# Board-Front.net
KiCad netlist of a schematic drawn in EAGLE
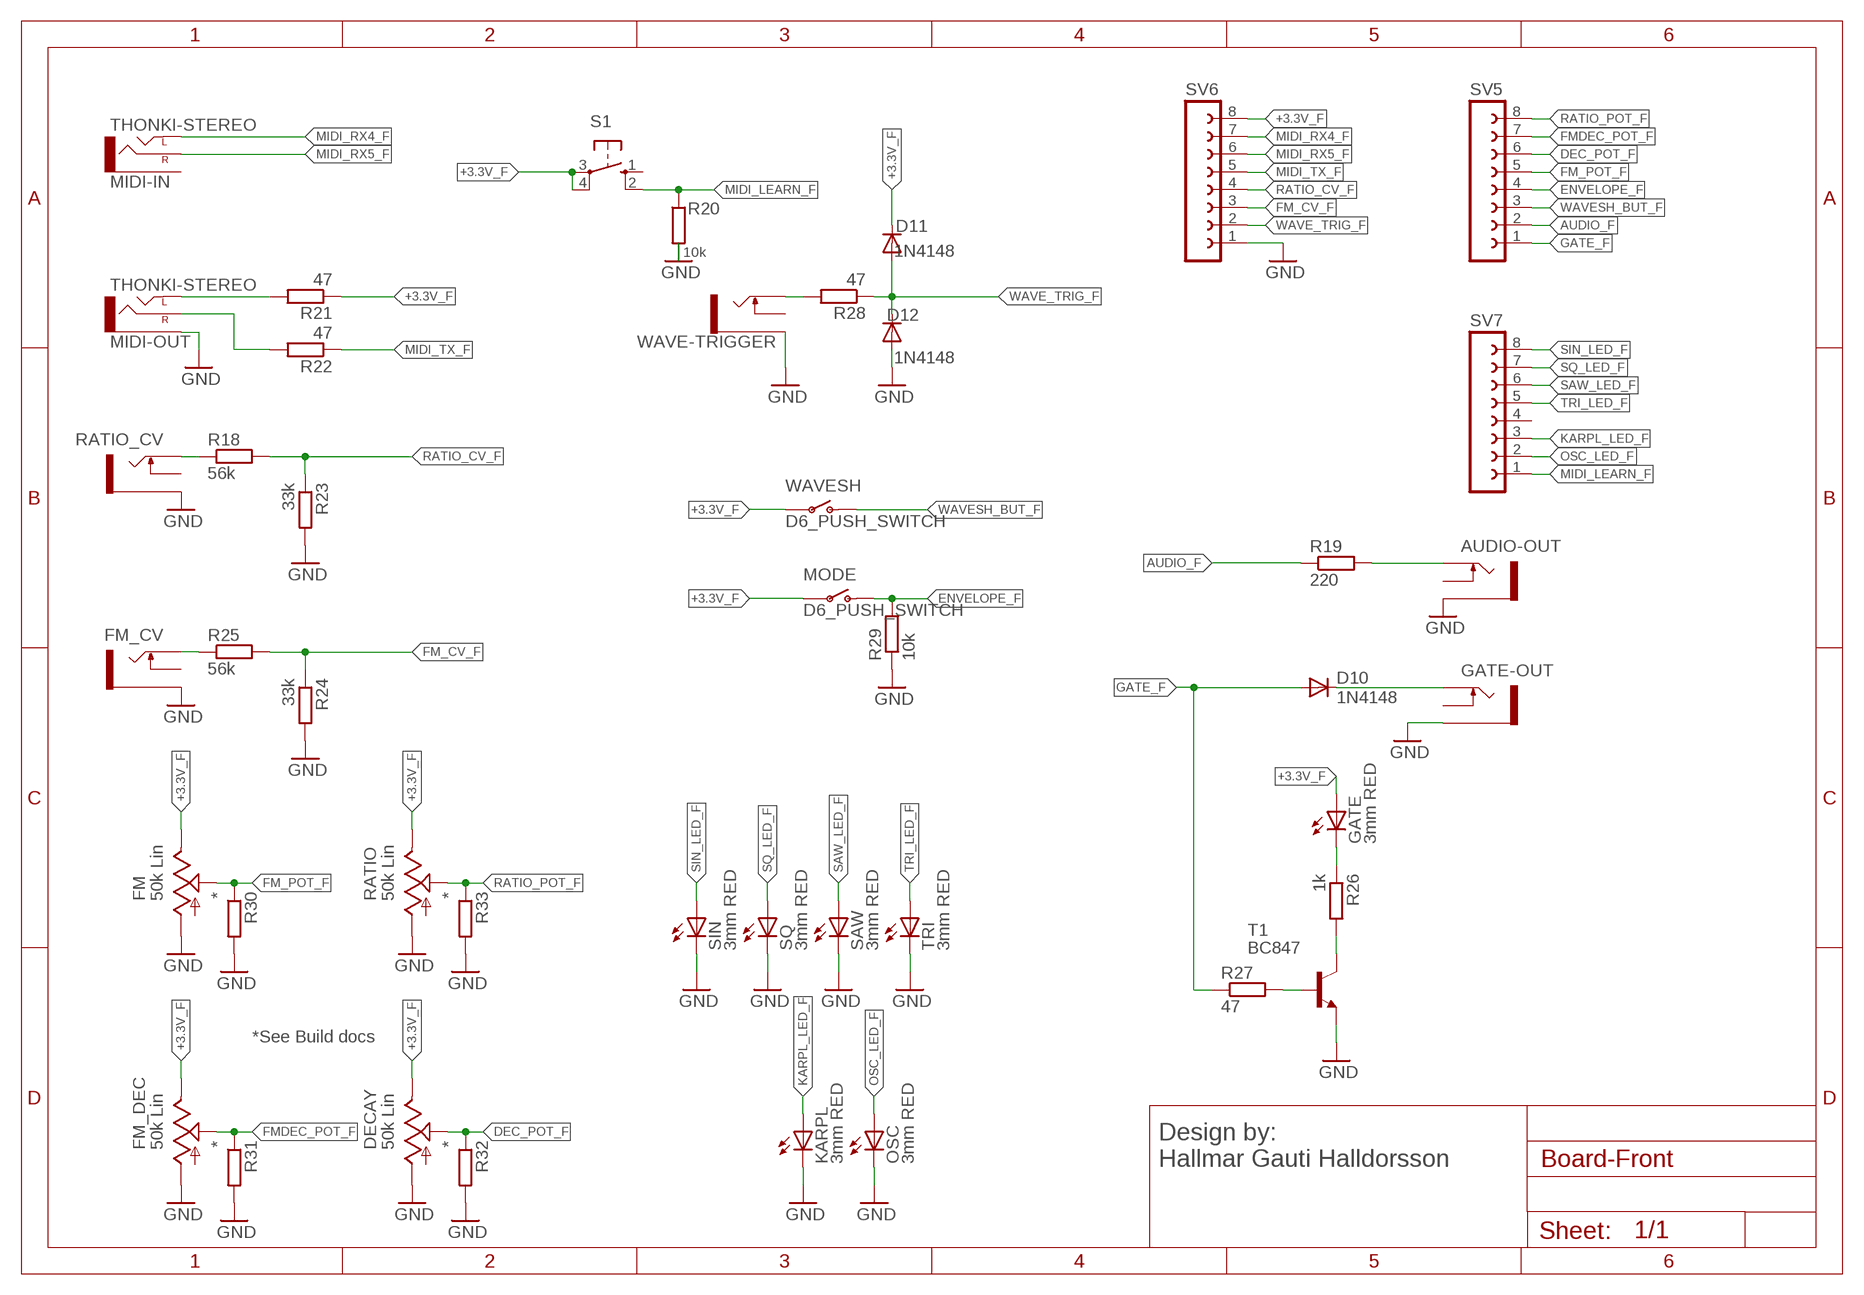
[diagram p0: schematic, sheet 1]

(export (version "E")
  (design (tool "Eeschema 10.0.6"))
  (components
    (comp (ref "AUDIO-OUT")
      (value "THONKICONNNEW")
      (footprint "eagle-import:WQP-PJ301M-12_JACK")
      (libsource (lib "eagle-import") (part "THONKICONNNEW"))
    )
    (comp (ref "D10")
      (value "1N4148")
      (footprint "eagle-import:DO35-7")
      (libsource (lib "eagle-import") (part "1N4148DO35-7"))
    )
    (comp (ref "D11")
      (value "1N4148")
      (footprint "eagle-import:DO35-7")
      (libsource (lib "eagle-import") (part "1N4148DO35-7"))
    )
    (comp (ref "D12")
      (value "1N4148")
      (footprint "eagle-import:DO35-7")
      (libsource (lib "eagle-import") (part "1N4148DO35-7"))
    )
    (comp (ref "DECAY")
      (value "50k Lin")
      (footprint "eagle-import:9MM_SNAP-IN_POT")
      (libsource (lib "eagle-import") (part "9MM_SNAP-IN_POT_"))
    )
    (comp (ref "FM")
      (value "50k Lin")
      (footprint "eagle-import:9MM_SNAP-IN_POT")
      (libsource (lib "eagle-import") (part "9MM_SNAP-IN_POT_"))
    )
    (comp (ref "FM_CV")
      (value "THONKICONNNEW")
      (footprint "eagle-import:WQP-PJ301M-12_JACK")
      (libsource (lib "eagle-import") (part "THONKICONNNEW"))
    )
    (comp (ref "FM_DEC")
      (value "50k Lin")
      (footprint "eagle-import:9MM_SNAP-IN_POT")
      (libsource (lib "eagle-import") (part "9MM_SNAP-IN_POT_"))
    )
    (comp (ref "GATE")
      (value "3mm RED")
      (footprint "eagle-import:LED3MM")
      (libsource (lib "eagle-import") (part "LED3MM"))
    )
    (comp (ref "GATE-OUT")
      (value "THONKICONNNEW")
      (footprint "eagle-import:WQP-PJ301M-12_JACK")
      (libsource (lib "eagle-import") (part "THONKICONNNEW"))
    )
    (comp (ref "KARPL")
      (value "3mm RED")
      (footprint "eagle-import:LED3MM")
      (libsource (lib "eagle-import") (part "LED3MM"))
    )
    (comp (ref "MIDI-IN")
      (value "THONKI-STEREO")
      (footprint "eagle-import:WQP-PJ366ST_JACK")
      (libsource (lib "eagle-import") (part "THONKI-STEREO"))
    )
    (comp (ref "MIDI-OUT")
      (value "THONKI-STEREO")
      (footprint "eagle-import:WQP-PJ366ST_JACK")
      (libsource (lib "eagle-import") (part "THONKI-STEREO"))
    )
    (comp (ref "MODE")
      (value "D6_PUSH_SWITCH")
      (footprint "eagle-import:D6_PUSH_SWITCH")
      (libsource (lib "eagle-import") (part "D6_PUSH_SWITCH"))
    )
    (comp (ref "OSC")
      (value "3mm RED")
      (footprint "eagle-import:LED3MM")
      (libsource (lib "eagle-import") (part "LED3MM"))
    )
    (comp (ref "R18")
      (value "56k")
      (footprint "eagle-import:M1206")
      (libsource (lib "eagle-import") (part "R-EU_M1206"))
    )
    (comp (ref "R19")
      (value "220")
      (footprint "eagle-import:M1206")
      (libsource (lib "eagle-import") (part "R-EU_M1206"))
    )
    (comp (ref "R20")
      (value "10k")
      (footprint "eagle-import:M1206")
      (libsource (lib "eagle-import") (part "R-EU_M1206"))
    )
    (comp (ref "R21")
      (value "47")
      (footprint "eagle-import:M1206")
      (libsource (lib "eagle-import") (part "R-EU_M1206"))
    )
    (comp (ref "R22")
      (value "47")
      (footprint "eagle-import:M1206")
      (libsource (lib "eagle-import") (part "R-EU_M1206"))
    )
    (comp (ref "R23")
      (value "33k")
      (footprint "eagle-import:M1206")
      (libsource (lib "eagle-import") (part "R-EU_M1206"))
    )
    (comp (ref "R24")
      (value "33k")
      (footprint "eagle-import:M1206")
      (libsource (lib "eagle-import") (part "R-EU_M1206"))
    )
    (comp (ref "R25")
      (value "56k")
      (footprint "eagle-import:M1206")
      (libsource (lib "eagle-import") (part "R-EU_M1206"))
    )
    (comp (ref "R26")
      (value "1k")
      (footprint "eagle-import:M1206")
      (libsource (lib "eagle-import") (part "R-EU_M1206"))
    )
    (comp (ref "R27")
      (value "47")
      (footprint "eagle-import:M1206")
      (libsource (lib "eagle-import") (part "R-EU_M1206"))
    )
    (comp (ref "R28")
      (value "47")
      (footprint "eagle-import:M1206")
      (libsource (lib "eagle-import") (part "R-EU_M1206"))
    )
    (comp (ref "R29")
      (value "10k")
      (footprint "eagle-import:M1206")
      (libsource (lib "eagle-import") (part "R-EU_M1206"))
    )
    (comp (ref "R30")
      (value "*")
      (footprint "eagle-import:M1206")
      (libsource (lib "eagle-import") (part "R-EU_M1206"))
    )
    (comp (ref "R31")
      (value "*")
      (footprint "eagle-import:M1206")
      (libsource (lib "eagle-import") (part "R-EU_M1206"))
    )
    (comp (ref "R32")
      (value "*")
      (footprint "eagle-import:M1206")
      (libsource (lib "eagle-import") (part "R-EU_M1206"))
    )
    (comp (ref "R33")
      (value "*")
      (footprint "eagle-import:M1206")
      (libsource (lib "eagle-import") (part "R-EU_M1206"))
    )
    (comp (ref "RATIO")
      (value "50k Lin")
      (footprint "eagle-import:9MM_SNAP-IN_POT")
      (libsource (lib "eagle-import") (part "9MM_SNAP-IN_POT_"))
    )
    (comp (ref "RATIO_CV")
      (value "THONKICONNNEW")
      (footprint "eagle-import:WQP-PJ301M-12_JACK")
      (libsource (lib "eagle-import") (part "THONKICONNNEW"))
    )
    (comp (ref "S1")
      (value "10-XX")
      (footprint "eagle-import:B3F-10XX")
      (fields (field (name "MPN") "B3F-1000"))
      (libsource (lib "eagle-import") (part "10-XX"))
    )
    (comp (ref "SAW")
      (value "3mm RED")
      (footprint "eagle-import:LED3MM")
      (libsource (lib "eagle-import") (part "LED3MM"))
    )
    (comp (ref "SIN")
      (value "3mm RED")
      (footprint "eagle-import:LED3MM")
      (libsource (lib "eagle-import") (part "LED3MM"))
    )
    (comp (ref "SQ")
      (value "3mm RED")
      (footprint "eagle-import:LED3MM")
      (libsource (lib "eagle-import") (part "LED3MM"))
    )
    (comp (ref "SV5")
      (value "FE08-1")
      (footprint "eagle-import:FE08")
      (libsource (lib "eagle-import") (part "FE08-1"))
    )
    (comp (ref "SV6")
      (value "FE08-1")
      (footprint "eagle-import:FE08")
      (libsource (lib "eagle-import") (part "FE08-1"))
    )
    (comp (ref "SV7")
      (value "FE08-1")
      (footprint "eagle-import:FE08")
      (libsource (lib "eagle-import") (part "FE08-1"))
    )
    (comp (ref "T1")
      (value "BC847")
      (footprint "eagle-import:SOT23")
      (libsource (lib "eagle-import") (part "BC847"))
    )
    (comp (ref "TRI")
      (value "3mm RED")
      (footprint "eagle-import:LED3MM")
      (libsource (lib "eagle-import") (part "LED3MM"))
    )
    (comp (ref "WAVE-TRIGGER")
      (value "THONKICONNNEW")
      (footprint "eagle-import:WQP-PJ301M-12_JACK")
      (libsource (lib "eagle-import") (part "THONKICONNNEW"))
    )
    (comp (ref "WAVESH")
      (value "D6_PUSH_SWITCH")
      (footprint "eagle-import:D6_PUSH_SWITCH")
      (libsource (lib "eagle-import") (part "D6_PUSH_SWITCH"))
    )
  )
  (nets
    (net (code "1") (name "+3.3V_F") (class "Default")
      (node (ref "D11") (pin "C") (pinfunction "C_C") (pintype "passive"))
      (node (ref "DECAY") (pin "3") (pinfunction "E_3") (pintype "passive"))
      (node (ref "FM") (pin "3") (pinfunction "E_3") (pintype "passive"))
      (node (ref "FM_DEC") (pin "3") (pinfunction "E_3") (pintype "passive"))
      (node (ref "GATE") (pin "A") (pinfunction "A_A") (pintype "passive"))
      (node (ref "MODE") (pin "P$3") (pinfunction "P_P$3") (pintype "passive"))
      (node (ref "MODE") (pin "P$4") (pinfunction "P_P$4") (pintype "passive"))
      (node (ref "R21") (pin "1") (pinfunction "1_1") (pintype "passive"))
      (node (ref "RATIO") (pin "3") (pinfunction "E_3") (pintype "passive"))
      (node (ref "S1") (pin "3") (pinfunction "P_3") (pintype "passive"))
      (node (ref "S1") (pin "4") (pinfunction "P1_4") (pintype "passive"))
      (node (ref "SV6") (pin "8") (pinfunction "8_8") (pintype "passive"))
      (node (ref "WAVESH") (pin "P$3") (pinfunction "P_P$3") (pintype "passive"))
      (node (ref "WAVESH") (pin "P$4") (pinfunction "P_P$4") (pintype "passive"))
    )
    (net (code "2") (name "AUDIO_F") (class "Default")
      (node (ref "R19") (pin "1") (pinfunction "1_1") (pintype "passive"))
      (node (ref "SV5") (pin "2") (pinfunction "2_2") (pintype "passive"))
    )
    (net (code "3") (name "DEC_POT_F") (class "Default")
      (node (ref "DECAY") (pin "2") (pinfunction "S_2") (pintype "passive"))
      (node (ref "R32") (pin "1") (pinfunction "1_1") (pintype "passive"))
      (node (ref "SV5") (pin "6") (pinfunction "6_6") (pintype "passive"))
    )
    (net (code "4") (name "ENVELOPE_F") (class "Default")
      (node (ref "MODE") (pin "P$1") (pinfunction "O_P$1") (pintype "passive"))
      (node (ref "MODE") (pin "P$2") (pinfunction "O_P$2") (pintype "passive"))
      (node (ref "R29") (pin "2") (pinfunction "2_2") (pintype "passive"))
      (node (ref "SV5") (pin "4") (pinfunction "4_4") (pintype "passive"))
    )
    (net (code "5") (name "FMDEC_POT_F") (class "Default")
      (node (ref "FM_DEC") (pin "2") (pinfunction "S_2") (pintype "passive"))
      (node (ref "R31") (pin "1") (pinfunction "1_1") (pintype "passive"))
      (node (ref "SV5") (pin "7") (pinfunction "7_7") (pintype "passive"))
    )
    (net (code "6") (name "FM_CV_F") (class "Default")
      (node (ref "R24") (pin "1") (pinfunction "1_1") (pintype "passive"))
      (node (ref "R25") (pin "2") (pinfunction "2_2") (pintype "passive"))
      (node (ref "SV6") (pin "3") (pinfunction "3_3") (pintype "passive"))
    )
    (net (code "7") (name "FM_POT_F") (class "Default")
      (node (ref "FM") (pin "2") (pinfunction "S_2") (pintype "passive"))
      (node (ref "R30") (pin "1") (pinfunction "1_1") (pintype "passive"))
      (node (ref "SV5") (pin "5") (pinfunction "5_5") (pintype "passive"))
    )
    (net (code "8") (name "GATE_F") (class "Default")
      (node (ref "D10") (pin "A") (pinfunction "A_A") (pintype "passive"))
      (node (ref "R27") (pin "1") (pinfunction "1_1") (pintype "passive"))
      (node (ref "SV5") (pin "1") (pinfunction "1_1") (pintype "passive"))
    )
    (net (code "9") (name "GND") (class "Default")
      (node (ref "AUDIO-OUT") (pin "P$3_SLEEVE") (pinfunction "SLEEVE_P$3_SLEEVE") (pintype "passive"))
      (node (ref "D12") (pin "A") (pinfunction "A_A") (pintype "passive"))
      (node (ref "DECAY") (pin "1") (pinfunction "A_1") (pintype "passive"))
      (node (ref "FM") (pin "1") (pinfunction "A_1") (pintype "passive"))
      (node (ref "FM_CV") (pin "P$3_SLEEVE") (pinfunction "SLEEVE_P$3_SLEEVE") (pintype "passive"))
      (node (ref "FM_DEC") (pin "1") (pinfunction "A_1") (pintype "passive"))
      (node (ref "GATE-OUT") (pin "P$3_SLEEVE") (pinfunction "SLEEVE_P$3_SLEEVE") (pintype "passive"))
      (node (ref "KARPL") (pin "K") (pinfunction "C_K") (pintype "passive"))
      (node (ref "MIDI-OUT") (pin "P$3_SLEEVE") (pinfunction "SLEEVE_P$3_SLEEVE") (pintype "bidirectional"))
      (node (ref "OSC") (pin "K") (pinfunction "C_K") (pintype "passive"))
      (node (ref "R20") (pin "2") (pinfunction "2_2") (pintype "passive"))
      (node (ref "R23") (pin "2") (pinfunction "2_2") (pintype "passive"))
      (node (ref "R24") (pin "2") (pinfunction "2_2") (pintype "passive"))
      (node (ref "R29") (pin "1") (pinfunction "1_1") (pintype "passive"))
      (node (ref "R30") (pin "2") (pinfunction "2_2") (pintype "passive"))
      (node (ref "R31") (pin "2") (pinfunction "2_2") (pintype "passive"))
      (node (ref "R32") (pin "2") (pinfunction "2_2") (pintype "passive"))
      (node (ref "R33") (pin "2") (pinfunction "2_2") (pintype "passive"))
      (node (ref "RATIO") (pin "1") (pinfunction "A_1") (pintype "passive"))
      (node (ref "RATIO_CV") (pin "P$3_SLEEVE") (pinfunction "SLEEVE_P$3_SLEEVE") (pintype "passive"))
      (node (ref "SAW") (pin "K") (pinfunction "C_K") (pintype "passive"))
      (node (ref "SIN") (pin "K") (pinfunction "C_K") (pintype "passive"))
      (node (ref "SQ") (pin "K") (pinfunction "C_K") (pintype "passive"))
      (node (ref "SV6") (pin "1") (pinfunction "1_1") (pintype "passive"))
      (node (ref "T1") (pin "2") (pinfunction "E_2") (pintype "passive"))
      (node (ref "TRI") (pin "K") (pinfunction "C_K") (pintype "passive"))
      (node (ref "WAVE-TRIGGER") (pin "P$3_SLEEVE") (pinfunction "SLEEVE_P$3_SLEEVE") (pintype "passive"))
    )
    (net (code "10") (name "KARPL_LED_F") (class "Default")
      (node (ref "KARPL") (pin "A") (pinfunction "A_A") (pintype "passive"))
      (node (ref "SV7") (pin "3") (pinfunction "3_3") (pintype "passive"))
    )
    (net (code "11") (name "MIDI_LEARN_F") (class "Default")
      (node (ref "R20") (pin "1") (pinfunction "1_1") (pintype "passive"))
      (node (ref "S1") (pin "2") (pinfunction "S1_2") (pintype "passive"))
      (node (ref "SV7") (pin "1") (pinfunction "1_1") (pintype "passive"))
    )
    (net (code "12") (name "MIDI_RX4_F") (class "Default")
      (node (ref "MIDI-IN") (pin "P$1_TIP") (pinfunction "LEFT_P$1_TIP") (pintype "bidirectional"))
      (node (ref "SV6") (pin "7") (pinfunction "7_7") (pintype "passive"))
    )
    (net (code "13") (name "MIDI_RX5_F") (class "Default")
      (node (ref "MIDI-IN") (pin "P$2_SWITCH") (pinfunction "RIGHT_P$2_SWITCH") (pintype "bidirectional"))
      (node (ref "SV6") (pin "6") (pinfunction "6_6") (pintype "passive"))
    )
    (net (code "14") (name "MIDI_TX_F") (class "Default")
      (node (ref "R22") (pin "1") (pinfunction "1_1") (pintype "passive"))
      (node (ref "SV6") (pin "5") (pinfunction "5_5") (pintype "passive"))
    )
    (net (code "15") (name "Net-(AUDIO-OUT-TIP)") (class "Default")
      (node (ref "AUDIO-OUT") (pin "P$1_TIP") (pinfunction "TIP_P$1_TIP") (pintype "passive"))
      (node (ref "R19") (pin "2") (pinfunction "2_2") (pintype "passive"))
    )
    (net (code "16") (name "Net-(FM_CV-TIP)") (class "Default")
      (node (ref "FM_CV") (pin "P$1_TIP") (pinfunction "TIP_P$1_TIP") (pintype "passive"))
      (node (ref "R25") (pin "1") (pinfunction "1_1") (pintype "passive"))
    )
    (net (code "17") (name "Net-(GATE-C)") (class "Default")
      (node (ref "GATE") (pin "K") (pinfunction "C_K") (pintype "passive"))
      (node (ref "R26") (pin "1") (pinfunction "1_1") (pintype "passive"))
    )
    (net (code "18") (name "Net-(GATE-OUT-TIP)") (class "Default")
      (node (ref "D10") (pin "C") (pinfunction "C_C") (pintype "passive"))
      (node (ref "GATE-OUT") (pin "P$1_TIP") (pinfunction "TIP_P$1_TIP") (pintype "passive"))
    )
    (net (code "19") (name "Net-(MIDI-OUT-LEFT)") (class "Default")
      (node (ref "MIDI-OUT") (pin "P$1_TIP") (pinfunction "LEFT_P$1_TIP") (pintype "bidirectional"))
      (node (ref "R21") (pin "2") (pinfunction "2_2") (pintype "passive"))
    )
    (net (code "20") (name "Net-(MIDI-OUT-RIGHT)") (class "Default")
      (node (ref "MIDI-OUT") (pin "P$2_SWITCH") (pinfunction "RIGHT_P$2_SWITCH") (pintype "bidirectional"))
      (node (ref "R22") (pin "2") (pinfunction "2_2") (pintype "passive"))
    )
    (net (code "21") (name "Net-(RATIO_CV-TIP)") (class "Default")
      (node (ref "R18") (pin "1") (pinfunction "1_1") (pintype "passive"))
      (node (ref "RATIO_CV") (pin "P$1_TIP") (pinfunction "TIP_P$1_TIP") (pintype "passive"))
    )
    (net (code "22") (name "Net-(T1-B)") (class "Default")
      (node (ref "R27") (pin "2") (pinfunction "2_2") (pintype "passive"))
      (node (ref "T1") (pin "1") (pinfunction "B_1") (pintype "passive"))
    )
    (net (code "23") (name "Net-(T1-C)") (class "Default")
      (node (ref "R26") (pin "2") (pinfunction "2_2") (pintype "passive"))
      (node (ref "T1") (pin "3") (pinfunction "C_3") (pintype "passive"))
    )
    (net (code "24") (name "Net-(WAVE-TRIGGER-TIP)") (class "Default")
      (node (ref "R28") (pin "2") (pinfunction "2_2") (pintype "passive"))
      (node (ref "WAVE-TRIGGER") (pin "P$1_TIP") (pinfunction "TIP_P$1_TIP") (pintype "passive"))
    )
    (net (code "25") (name "OSC_LED_F") (class "Default")
      (node (ref "OSC") (pin "A") (pinfunction "A_A") (pintype "passive"))
      (node (ref "SV7") (pin "2") (pinfunction "2_2") (pintype "passive"))
    )
    (net (code "26") (name "RATIO_CV_F") (class "Default")
      (node (ref "R18") (pin "2") (pinfunction "2_2") (pintype "passive"))
      (node (ref "R23") (pin "1") (pinfunction "1_1") (pintype "passive"))
      (node (ref "SV6") (pin "4") (pinfunction "4_4") (pintype "passive"))
    )
    (net (code "27") (name "RATIO_POT_F") (class "Default")
      (node (ref "R33") (pin "1") (pinfunction "1_1") (pintype "passive"))
      (node (ref "RATIO") (pin "2") (pinfunction "S_2") (pintype "passive"))
      (node (ref "SV5") (pin "8") (pinfunction "8_8") (pintype "passive"))
    )
    (net (code "28") (name "SAW_LED_F") (class "Default")
      (node (ref "SAW") (pin "A") (pinfunction "A_A") (pintype "passive"))
      (node (ref "SV7") (pin "6") (pinfunction "6_6") (pintype "passive"))
    )
    (net (code "29") (name "SIN_LED_F") (class "Default")
      (node (ref "SIN") (pin "A") (pinfunction "A_A") (pintype "passive"))
      (node (ref "SV7") (pin "8") (pinfunction "8_8") (pintype "passive"))
    )
    (net (code "30") (name "SQ_LED_F") (class "Default")
      (node (ref "SQ") (pin "A") (pinfunction "A_A") (pintype "passive"))
      (node (ref "SV7") (pin "7") (pinfunction "7_7") (pintype "passive"))
    )
    (net (code "31") (name "TRI_LED_F") (class "Default")
      (node (ref "SV7") (pin "5") (pinfunction "5_5") (pintype "passive"))
      (node (ref "TRI") (pin "A") (pinfunction "A_A") (pintype "passive"))
    )
    (net (code "32") (name "WAVESH_BUT_F") (class "Default")
      (node (ref "SV5") (pin "3") (pinfunction "3_3") (pintype "passive"))
      (node (ref "WAVESH") (pin "P$1") (pinfunction "O_P$1") (pintype "passive"))
      (node (ref "WAVESH") (pin "P$2") (pinfunction "O_P$2") (pintype "passive"))
    )
    (net (code "33") (name "WAVE_TRIG_F") (class "Default")
      (node (ref "D11") (pin "A") (pinfunction "A_A") (pintype "passive"))
      (node (ref "D12") (pin "C") (pinfunction "C_C") (pintype "passive"))
      (node (ref "R28") (pin "1") (pinfunction "1_1") (pintype "passive"))
      (node (ref "SV6") (pin "2") (pinfunction "2_2") (pintype "passive"))
    )
    (net (code "34") (name "unconnected-(AUDIO-OUT-SWITCH-PadP$2_SWITCH)") (class "Default")
      (node (ref "AUDIO-OUT") (pin "P$2_SWITCH") (pinfunction "SWITCH_P$2_SWITCH") (pintype "passive"))
    )
    (net (code "35") (name "unconnected-(FM_CV-SWITCH-PadP$2_SWITCH)") (class "Default")
      (node (ref "FM_CV") (pin "P$2_SWITCH") (pinfunction "SWITCH_P$2_SWITCH") (pintype "passive"))
    )
    (net (code "36") (name "unconnected-(GATE-OUT-SWITCH-PadP$2_SWITCH)") (class "Default")
      (node (ref "GATE-OUT") (pin "P$2_SWITCH") (pinfunction "SWITCH_P$2_SWITCH") (pintype "passive"))
    )
    (net (code "37") (name "unconnected-(MIDI-IN-SLEEVE-PadP$3_SLEEVE)") (class "Default")
      (node (ref "MIDI-IN") (pin "P$3_SLEEVE") (pinfunction "SLEEVE_P$3_SLEEVE") (pintype "bidirectional"))
    )
    (net (code "38") (name "unconnected-(RATIO_CV-SWITCH-PadP$2_SWITCH)") (class "Default")
      (node (ref "RATIO_CV") (pin "P$2_SWITCH") (pinfunction "SWITCH_P$2_SWITCH") (pintype "passive"))
    )
    (net (code "39") (name "unconnected-(S1-S-Pad1)") (class "Default")
      (node (ref "S1") (pin "1") (pinfunction "S_1") (pintype "passive"))
    )
    (net (code "40") (name "unconnected-(SV7-Pad4)") (class "Default")
      (node (ref "SV7") (pin "4") (pinfunction "4_4") (pintype "passive"))
    )
    (net (code "41") (name "unconnected-(WAVE-TRIGGER-SWITCH-PadP$2_SWITCH)") (class "Default")
      (node (ref "WAVE-TRIGGER") (pin "P$2_SWITCH") (pinfunction "SWITCH_P$2_SWITCH") (pintype "passive"))
    )
  )
)
